# FINAL_1_withhbridge.net
KiCad netlist of a schematic drawn in EAGLE
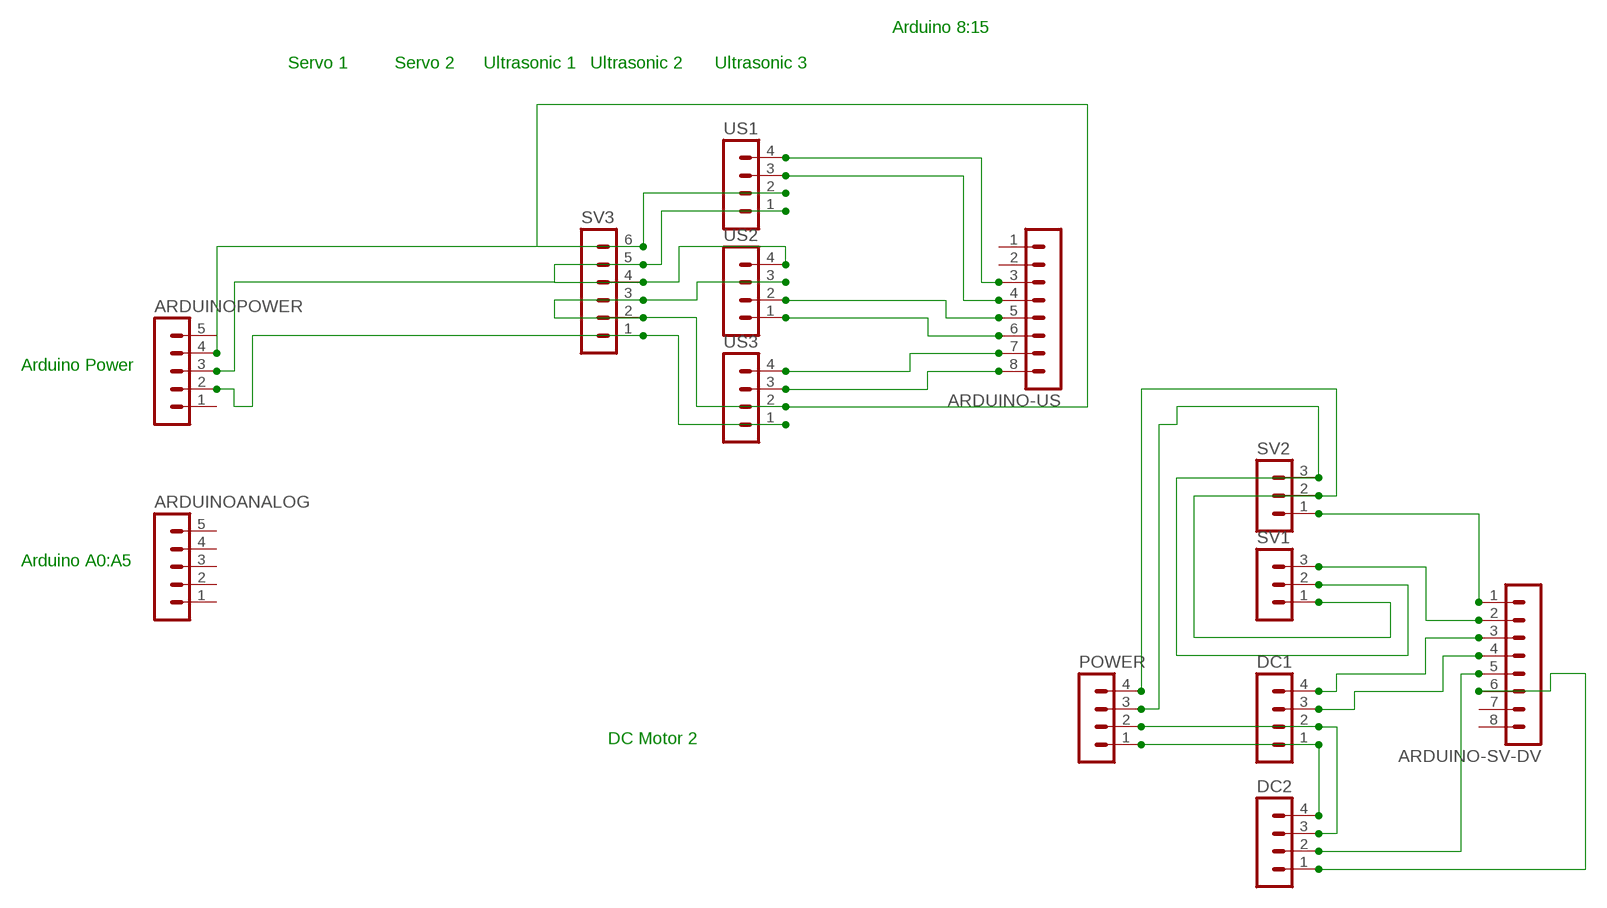
[diagram p0: schematic, sheet 1]

(export (version "E")
  (design (tool "Eeschema 10.0.6"))
  (components
    (comp (ref "ARDUINO-SV-DV")
      (value "MA08-1W")
      (footprint "eagle-import:MA08-1W")
      (libsource (lib "eagle-import") (part "MA08-1W"))
    )
    (comp (ref "ARDUINO-US")
      (value "MA08-1W")
      (footprint "eagle-import:MA08-1W")
      (libsource (lib "eagle-import") (part "MA08-1W"))
    )
    (comp (ref "ARDUINOANALOG")
      (value "MA05-1")
      (footprint "eagle-import:MA05-1")
      (libsource (lib "eagle-import") (part "MA05-1"))
    )
    (comp (ref "ARDUINOPOWER")
      (value "MA05-1")
      (footprint "eagle-import:MA05-1")
      (libsource (lib "eagle-import") (part "MA05-1"))
    )
    (comp (ref "DC1")
      (value "MA04-1")
      (footprint "eagle-import:MA04-1")
      (libsource (lib "eagle-import") (part "MA04-1"))
    )
    (comp (ref "DC2")
      (value "MA04-1")
      (footprint "eagle-import:MA04-1")
      (libsource (lib "eagle-import") (part "MA04-1"))
    )
    (comp (ref "POWER")
      (value "MA04-1")
      (footprint "eagle-import:MA04-1")
      (libsource (lib "eagle-import") (part "MA04-1"))
    )
    (comp (ref "SV1")
      (value "MA03-1")
      (footprint "eagle-import:MA03-1")
      (libsource (lib "eagle-import") (part "MA03-1"))
    )
    (comp (ref "SV2")
      (value "MA03-1")
      (footprint "eagle-import:MA03-1")
      (libsource (lib "eagle-import") (part "MA03-1"))
    )
    (comp (ref "SV3")
      (value "MA06-1")
      (footprint "eagle-import:MA06-1")
      (libsource (lib "eagle-import") (part "MA06-1"))
    )
    (comp (ref "US1")
      (value "MA04-1")
      (footprint "eagle-import:MA04-1")
      (libsource (lib "eagle-import") (part "MA04-1"))
    )
    (comp (ref "US2")
      (value "MA04-1")
      (footprint "eagle-import:MA04-1")
      (libsource (lib "eagle-import") (part "MA04-1"))
    )
    (comp (ref "US3")
      (value "MA04-1")
      (footprint "eagle-import:MA04-1")
      (libsource (lib "eagle-import") (part "MA04-1"))
    )
  )
  (nets
    (net (code "1") (name "Net-(ARDUINO-SV-DV-Pad1)") (class "Default")
      (node (ref "ARDUINO-SV-DV") (pin "1") (pinfunction "1_1") (pintype "passive"))
      (node (ref "SV2") (pin "1") (pinfunction "1_1") (pintype "passive"))
    )
    (net (code "2") (name "Net-(ARDUINO-SV-DV-Pad2)") (class "Default")
      (node (ref "ARDUINO-SV-DV") (pin "2") (pinfunction "2_2") (pintype "passive"))
      (node (ref "SV1") (pin "3") (pinfunction "3_3") (pintype "passive"))
    )
    (net (code "3") (name "Net-(ARDUINO-SV-DV-Pad3)") (class "Default")
      (node (ref "ARDUINO-SV-DV") (pin "3") (pinfunction "3_3") (pintype "passive"))
      (node (ref "DC1") (pin "4") (pinfunction "4_4") (pintype "passive"))
    )
    (net (code "4") (name "Net-(ARDUINO-SV-DV-Pad4)") (class "Default")
      (node (ref "ARDUINO-SV-DV") (pin "4") (pinfunction "4_4") (pintype "passive"))
      (node (ref "DC1") (pin "3") (pinfunction "3_3") (pintype "passive"))
    )
    (net (code "5") (name "Net-(ARDUINO-SV-DV-Pad5)") (class "Default")
      (node (ref "ARDUINO-SV-DV") (pin "5") (pinfunction "5_5") (pintype "passive"))
      (node (ref "DC2") (pin "2") (pinfunction "2_2") (pintype "passive"))
    )
    (net (code "6") (name "Net-(ARDUINO-SV-DV-Pad6)") (class "Default")
      (node (ref "ARDUINO-SV-DV") (pin "6") (pinfunction "6_6") (pintype "passive"))
      (node (ref "DC2") (pin "1") (pinfunction "1_1") (pintype "passive"))
    )
    (net (code "7") (name "Net-(ARDUINO-US-Pad3)") (class "Default")
      (node (ref "ARDUINO-US") (pin "3") (pinfunction "3_3") (pintype "passive"))
      (node (ref "US1") (pin "4") (pinfunction "4_4") (pintype "passive"))
    )
    (net (code "8") (name "Net-(ARDUINO-US-Pad4)") (class "Default")
      (node (ref "ARDUINO-US") (pin "4") (pinfunction "4_4") (pintype "passive"))
      (node (ref "US1") (pin "3") (pinfunction "3_3") (pintype "passive"))
    )
    (net (code "9") (name "Net-(ARDUINO-US-Pad5)") (class "Default")
      (node (ref "ARDUINO-US") (pin "5") (pinfunction "5_5") (pintype "passive"))
      (node (ref "US2") (pin "2") (pinfunction "2_2") (pintype "passive"))
    )
    (net (code "10") (name "Net-(ARDUINO-US-Pad6)") (class "Default")
      (node (ref "ARDUINO-US") (pin "6") (pinfunction "6_6") (pintype "passive"))
      (node (ref "US2") (pin "1") (pinfunction "1_1") (pintype "passive"))
    )
    (net (code "11") (name "Net-(ARDUINO-US-Pad7)") (class "Default")
      (node (ref "ARDUINO-US") (pin "7") (pinfunction "7_7") (pintype "passive"))
      (node (ref "US3") (pin "4") (pinfunction "4_4") (pintype "passive"))
    )
    (net (code "12") (name "Net-(ARDUINO-US-Pad8)") (class "Default")
      (node (ref "ARDUINO-US") (pin "8") (pinfunction "8_8") (pintype "passive"))
      (node (ref "US3") (pin "3") (pinfunction "3_3") (pintype "passive"))
    )
    (net (code "13") (name "Net-(ARDUINOPOWER-Pad2)") (class "Default")
      (node (ref "ARDUINOPOWER") (pin "2") (pinfunction "2_2") (pintype "passive"))
      (node (ref "SV3") (pin "1") (pinfunction "1_1") (pintype "passive"))
      (node (ref "US3") (pin "1") (pinfunction "1_1") (pintype "passive"))
    )
    (net (code "14") (name "Net-(ARDUINOPOWER-Pad3)") (class "Default")
      (node (ref "ARDUINOPOWER") (pin "3") (pinfunction "3_3") (pintype "passive"))
      (node (ref "SV3") (pin "4") (pinfunction "4_4") (pintype "passive"))
      (node (ref "SV3") (pin "5") (pinfunction "5_5") (pintype "passive"))
      (node (ref "US1") (pin "1") (pinfunction "1_1") (pintype "passive"))
      (node (ref "US2") (pin "4") (pinfunction "4_4") (pintype "passive"))
    )
    (net (code "15") (name "Net-(ARDUINOPOWER-Pad4)") (class "Default")
      (node (ref "ARDUINOPOWER") (pin "4") (pinfunction "4_4") (pintype "passive"))
      (node (ref "SV3") (pin "2") (pinfunction "2_2") (pintype "passive"))
      (node (ref "SV3") (pin "3") (pinfunction "3_3") (pintype "passive"))
      (node (ref "SV3") (pin "6") (pinfunction "6_6") (pintype "passive"))
      (node (ref "US1") (pin "2") (pinfunction "2_2") (pintype "passive"))
      (node (ref "US2") (pin "3") (pinfunction "3_3") (pintype "passive"))
      (node (ref "US3") (pin "2") (pinfunction "2_2") (pintype "passive"))
    )
    (net (code "16") (name "Net-(DC1-Pad1)") (class "Default")
      (node (ref "DC1") (pin "1") (pinfunction "1_1") (pintype "passive"))
      (node (ref "DC2") (pin "4") (pinfunction "4_4") (pintype "passive"))
      (node (ref "POWER") (pin "1") (pinfunction "1_1") (pintype "passive"))
    )
    (net (code "17") (name "Net-(DC1-Pad2)") (class "Default")
      (node (ref "DC1") (pin "2") (pinfunction "2_2") (pintype "passive"))
      (node (ref "DC2") (pin "3") (pinfunction "3_3") (pintype "passive"))
      (node (ref "POWER") (pin "2") (pinfunction "2_2") (pintype "passive"))
    )
    (net (code "18") (name "Net-(POWER-Pad3)") (class "Default")
      (node (ref "POWER") (pin "3") (pinfunction "3_3") (pintype "passive"))
      (node (ref "SV1") (pin "2") (pinfunction "2_2") (pintype "passive"))
      (node (ref "SV2") (pin "3") (pinfunction "3_3") (pintype "passive"))
    )
    (net (code "19") (name "Net-(POWER-Pad4)") (class "Default")
      (node (ref "POWER") (pin "4") (pinfunction "4_4") (pintype "passive"))
      (node (ref "SV1") (pin "1") (pinfunction "1_1") (pintype "passive"))
      (node (ref "SV2") (pin "2") (pinfunction "2_2") (pintype "passive"))
    )
    (net (code "20") (name "unconnected-(ARDUINO-SV-DV-Pad7)") (class "Default")
      (node (ref "ARDUINO-SV-DV") (pin "7") (pinfunction "7_7") (pintype "passive"))
    )
    (net (code "21") (name "unconnected-(ARDUINO-SV-DV-Pad8)") (class "Default")
      (node (ref "ARDUINO-SV-DV") (pin "8") (pinfunction "8_8") (pintype "passive"))
    )
    (net (code "22") (name "unconnected-(ARDUINO-US-Pad1)") (class "Default")
      (node (ref "ARDUINO-US") (pin "1") (pinfunction "1_1") (pintype "passive"))
    )
    (net (code "23") (name "unconnected-(ARDUINO-US-Pad2)") (class "Default")
      (node (ref "ARDUINO-US") (pin "2") (pinfunction "2_2") (pintype "passive"))
    )
    (net (code "24") (name "unconnected-(ARDUINOANALOG-Pad1)") (class "Default")
      (node (ref "ARDUINOANALOG") (pin "1") (pinfunction "1_1") (pintype "passive"))
    )
    (net (code "25") (name "unconnected-(ARDUINOANALOG-Pad2)") (class "Default")
      (node (ref "ARDUINOANALOG") (pin "2") (pinfunction "2_2") (pintype "passive"))
    )
    (net (code "26") (name "unconnected-(ARDUINOANALOG-Pad3)") (class "Default")
      (node (ref "ARDUINOANALOG") (pin "3") (pinfunction "3_3") (pintype "passive"))
    )
    (net (code "27") (name "unconnected-(ARDUINOANALOG-Pad4)") (class "Default")
      (node (ref "ARDUINOANALOG") (pin "4") (pinfunction "4_4") (pintype "passive"))
    )
    (net (code "28") (name "unconnected-(ARDUINOANALOG-Pad5)") (class "Default")
      (node (ref "ARDUINOANALOG") (pin "5") (pinfunction "5_5") (pintype "passive"))
    )
    (net (code "29") (name "unconnected-(ARDUINOPOWER-Pad1)") (class "Default")
      (node (ref "ARDUINOPOWER") (pin "1") (pinfunction "1_1") (pintype "passive"))
    )
    (net (code "30") (name "unconnected-(ARDUINOPOWER-Pad5)") (class "Default")
      (node (ref "ARDUINOPOWER") (pin "5") (pinfunction "5_5") (pintype "passive"))
    )
  )
)
